# MCU.net
KiCad netlist of a schematic drawn in Altium Designer
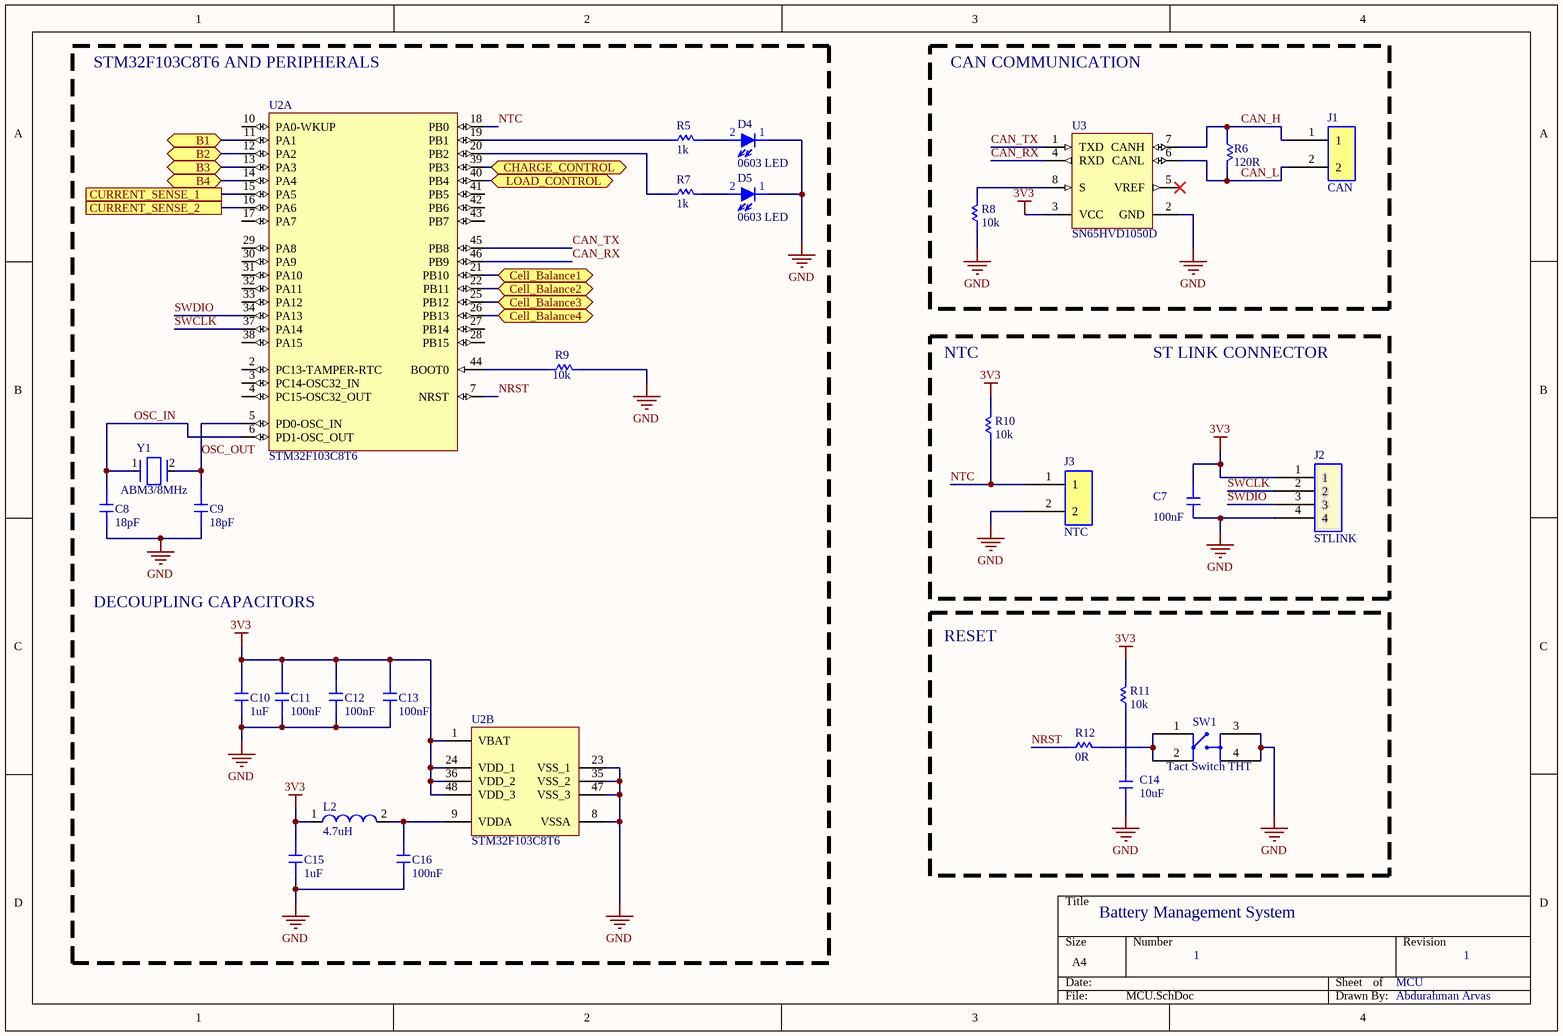
[diagram p0: MCU.SchDoc]

(export (version "E")
  (design (tool "Eeschema 10.0.6"))
  (components
    (comp (ref "C7")
      (value "100nF")
      (footprint "C0805")
      (libsource (lib "Arvas_AltiumSCH") (part "SMD_Capacitor"))
    )
    (comp (ref "C8")
      (value "18pF")
      (footprint "C0603")
      (libsource (lib "Arvas_AltiumSCH") (part "SMD_Capacitor"))
    )
    (comp (ref "C9")
      (value "18pF")
      (footprint "C0603")
      (libsource (lib "Arvas_AltiumSCH") (part "SMD_Capacitor"))
    )
    (comp (ref "C10")
      (value "1uF")
      (footprint "C0805")
      (libsource (lib "Arvas_AltiumSCH") (part "SMD_Capacitor"))
    )
    (comp (ref "C11")
      (value "100nF")
      (footprint "C0805")
      (libsource (lib "Arvas_AltiumSCH") (part "SMD_Capacitor"))
    )
    (comp (ref "C12")
      (value "100nF")
      (footprint "C0805")
      (libsource (lib "Arvas_AltiumSCH") (part "SMD_Capacitor"))
    )
    (comp (ref "C13")
      (value "100nF")
      (footprint "C0805")
      (libsource (lib "Arvas_AltiumSCH") (part "SMD_Capacitor"))
    )
    (comp (ref "C14")
      (value "10uF")
      (footprint "C0805")
      (libsource (lib "Arvas_AltiumSCH") (part "SMD_Capacitor"))
    )
    (comp (ref "C15")
      (value "1uF")
      (footprint "C0805")
      (libsource (lib "Arvas_AltiumSCH") (part "SMD_Capacitor"))
    )
    (comp (ref "C16")
      (value "100nF")
      (footprint "C0805")
      (libsource (lib "Arvas_AltiumSCH") (part "SMD_Capacitor"))
    )
    (comp (ref "D4")
      (value "0603 LED")
      (footprint "LED_0603")
      (description "Light Emitting Diode with 0603 footprint.")
      (libsource (lib "Arvas_AltiumSCH") (part "Led 0603"))
    )
    (comp (ref "D5")
      (value "0603 LED")
      (footprint "LED_0603")
      (description "Light Emitting Diode with 0603 footprint.")
      (libsource (lib "Arvas_AltiumSCH") (part "Led 0603"))
    )
    (comp (ref "J1")
      (value "CAN")
      (footprint "CONN X2")
      (description "İki Pin Connector")
      (libsource (lib "Arvas_AltiumSCH") (part "CONN X2_1"))
    )
    (comp (ref "J2")
      (value "STLINK")
      (footprint "CONN X4")
      (description "x4 Pin Header")
      (libsource (lib "Arvas_AltiumSCH") (part "CONN X4"))
    )
    (comp (ref "J3")
      (value "NTC")
      (footprint "CONN X2")
      (description "İki Pin Connector")
      (libsource (lib "Arvas_AltiumSCH") (part "CONN X2_1"))
    )
    (comp (ref "L2")
      (value "4.7uH")
      (footprint "SMD-0805")
      (description "SMD-Multilayer Inductor WE-MI, L = 1.00 µH")
      (libsource (lib "Altium Content Vault") (part "PAS-IND-INDUCTOR-2"))
    )
    (comp (ref "R5")
      (value "1k")
      (footprint "R0603")
      (description "SMD Chip Resistor")
      (libsource (lib "Arvas_AltiumSCH") (part "SMD Resistor"))
    )
    (comp (ref "R6")
      (value "120R")
      (footprint "R0805")
      (description "SMD Chip Resistor")
      (libsource (lib "Arvas_AltiumSCH") (part "SMD Resistor"))
    )
    (comp (ref "R7")
      (value "1k")
      (footprint "R0603")
      (description "SMD Chip Resistor")
      (libsource (lib "Arvas_AltiumSCH") (part "SMD Resistor"))
    )
    (comp (ref "R8")
      (value "10k")
      (footprint "R0805")
      (description "SMD Chip Resistor")
      (libsource (lib "Arvas_AltiumSCH") (part "SMD Resistor"))
    )
    (comp (ref "R9")
      (value "10k")
      (footprint "R0805")
      (description "SMD Chip Resistor")
      (libsource (lib "Arvas_AltiumSCH") (part "SMD Resistor"))
    )
    (comp (ref "R10")
      (value "10k")
      (footprint "R0805")
      (description "SMD Chip Resistor")
      (libsource (lib "Arvas_AltiumSCH") (part "SMD Resistor"))
    )
    (comp (ref "R11")
      (value "10k")
      (footprint "R0805")
      (description "SMD Chip Resistor")
      (libsource (lib "Arvas_AltiumSCH") (part "SMD Resistor"))
    )
    (comp (ref "R12")
      (value "0R")
      (footprint "R0805")
      (description "SMD Chip Resistor")
      (libsource (lib "Arvas_AltiumSCH") (part "SMD Resistor"))
    )
    (comp (ref "SW1")
      (value "Tact Switch THT")
      (footprint "Tact Switch 6x6 mm")
      (description "Tact Switch 6x6 mm")
      (libsource (lib "Arvas_AltiumSCH") (part "Tact Switch THT"))
    )
    (comp (ref "U2")
      (value "STM32F103C8T6")
      (footprint "STM-LQFP48_L")
      (libsource (lib "Altium Content Vault") (part "MC-ARM-STM32F103X8_B-SQ48"))
    )
    (comp (ref "U3")
      (value "SN65HVD1050D")
      (footprint "D0008A_N")
      (fields (field (name "MANUFACTURER") "Texas Instruments"))
      (libsource (lib "Altium Content Vault") (part "TI-SN65HVD1050-SOIC_D-8"))
    )
    (comp (ref "Y1")
      (value "ABM3/8MHz")
      (footprint "FP-ABM3-MFG")
      (description "Crystal 8MHz ±20ppm 18pF SMD-2 5mm x 3.2mm")
      (fields (field (name "TOLERANCE") "20ppm"))
      (libsource (lib "Altium Content Vault") (part "c23a69dc6c9e2f18f2079038eb95dd1"))
    )
  )
  (nets
    (net (code "1") (name "/B1") (class "Default")
      (node (ref "U2") (pin "11") (pinfunction "PA1_11") (pintype "bidirectional"))
    )
    (net (code "2") (name "/B2") (class "Default")
      (node (ref "U2") (pin "12") (pinfunction "PA2_12") (pintype "bidirectional"))
    )
    (net (code "3") (name "/B3") (class "Default")
      (node (ref "U2") (pin "13") (pinfunction "PA3_13") (pintype "bidirectional"))
    )
    (net (code "4") (name "/B4") (class "Default")
      (node (ref "U2") (pin "14") (pinfunction "PA4_14") (pintype "bidirectional"))
    )
    (net (code "5") (name "/CAN_H") (class "Default")
      (node (ref "J1") (pin "1") (pinfunction "1_1") (pintype "passive"))
      (node (ref "R6") (pin "1") (pinfunction "1_1") (pintype "passive"))
      (node (ref "U3") (pin "7") (pinfunction "CANH_7") (pintype "bidirectional"))
    )
    (net (code "6") (name "/CAN_L") (class "Default")
      (node (ref "J1") (pin "2") (pinfunction "2_2") (pintype "passive"))
      (node (ref "R6") (pin "2") (pinfunction "2_2") (pintype "passive"))
      (node (ref "U3") (pin "6") (pinfunction "CANL_6") (pintype "bidirectional"))
    )
    (net (code "7") (name "/CAN_RX") (class "Default")
      (node (ref "U2") (pin "46") (pinfunction "PB9_46") (pintype "bidirectional"))
      (node (ref "U3") (pin "4") (pinfunction "RXD_4") (pintype "output"))
    )
    (net (code "8") (name "/CAN_TX") (class "Default")
      (node (ref "U2") (pin "45") (pinfunction "PB8_45") (pintype "bidirectional"))
      (node (ref "U3") (pin "1") (pinfunction "TXD_1") (pintype "input"))
    )
    (net (code "9") (name "/CHARGE_CONTROL") (class "Default")
      (node (ref "U2") (pin "39") (pinfunction "PB3_39") (pintype "bidirectional"))
    )
    (net (code "10") (name "/CURRENT_SENSE_1") (class "Default")
      (node (ref "U2") (pin "15") (pinfunction "PA5_15") (pintype "bidirectional"))
    )
    (net (code "11") (name "/CURRENT_SENSE_2") (class "Default")
      (node (ref "U2") (pin "16") (pinfunction "PA6_16") (pintype "bidirectional"))
    )
    (net (code "12") (name "/Cell_Balance1") (class "Default")
      (node (ref "U2") (pin "21") (pinfunction "PB10_21") (pintype "bidirectional"))
    )
    (net (code "13") (name "/Cell_Balance2") (class "Default")
      (node (ref "U2") (pin "22") (pinfunction "PB11_22") (pintype "bidirectional"))
    )
    (net (code "14") (name "/Cell_Balance3") (class "Default")
      (node (ref "U2") (pin "25") (pinfunction "PB12_25") (pintype "bidirectional"))
    )
    (net (code "15") (name "/Cell_Balance4") (class "Default")
      (node (ref "U2") (pin "26") (pinfunction "PB13_26") (pintype "bidirectional"))
    )
    (net (code "16") (name "/LOAD_CONTROL") (class "Default")
      (node (ref "U2") (pin "40") (pinfunction "PB4_40") (pintype "bidirectional"))
    )
    (net (code "17") (name "/NRST") (class "Default")
      (node (ref "R12") (pin "1") (pinfunction "1_1") (pintype "passive"))
      (node (ref "U2") (pin "7") (pinfunction "NRST_7") (pintype "bidirectional"))
    )
    (net (code "18") (name "/NTC") (class "Default")
      (node (ref "J3") (pin "1") (pinfunction "1_1") (pintype "passive"))
      (node (ref "R10") (pin "1") (pinfunction "1_1") (pintype "passive"))
      (node (ref "U2") (pin "18") (pinfunction "PB0_18") (pintype "bidirectional"))
    )
    (net (code "19") (name "/OSC_IN") (class "Default")
      (node (ref "C8") (pin "2") (pinfunction "2_2") (pintype "passive"))
      (node (ref "U2") (pin "6") (pinfunction "PD1-OSC_OUT_6") (pintype "bidirectional"))
      (node (ref "Y1") (pin "1") (pinfunction "1_1") (pintype "passive"))
    )
    (net (code "20") (name "/OSC_OUT") (class "Default")
      (node (ref "C9") (pin "2") (pinfunction "2_2") (pintype "passive"))
      (node (ref "U2") (pin "5") (pinfunction "PD0-OSC_IN_5") (pintype "bidirectional"))
      (node (ref "Y1") (pin "2") (pinfunction "2_2") (pintype "passive"))
    )
    (net (code "21") (name "/SWCLK") (class "Default")
      (node (ref "J2") (pin "2") (pinfunction "2_2") (pintype "passive"))
      (node (ref "U2") (pin "37") (pinfunction "PA14_37") (pintype "bidirectional"))
    )
    (net (code "22") (name "/SWDIO") (class "Default")
      (node (ref "J2") (pin "3") (pinfunction "3_3") (pintype "passive"))
      (node (ref "U2") (pin "34") (pinfunction "PA13_34") (pintype "bidirectional"))
    )
    (net (code "23") (name "3V3") (class "Default")
      (node (ref "C10") (pin "2") (pinfunction "2_2") (pintype "passive"))
      (node (ref "C11") (pin "2") (pinfunction "2_2") (pintype "passive"))
      (node (ref "C12") (pin "2") (pinfunction "2_2") (pintype "passive"))
      (node (ref "C13") (pin "2") (pinfunction "2_2") (pintype "passive"))
      (node (ref "C15") (pin "2") (pinfunction "2_2") (pintype "passive"))
      (node (ref "C7") (pin "2") (pinfunction "2_2") (pintype "passive"))
      (node (ref "J2") (pin "1") (pinfunction "1_1") (pintype "passive"))
      (node (ref "L2") (pin "1") (pinfunction "1_1") (pintype "passive"))
      (node (ref "R10") (pin "2") (pinfunction "2_2") (pintype "passive"))
      (node (ref "R11") (pin "2") (pinfunction "2_2") (pintype "passive"))
      (node (ref "U2") (pin "1") (pinfunction "VBAT_1") (pintype "power_in"))
      (node (ref "U2") (pin "24") (pinfunction "VDD_1_24") (pintype "power_in"))
      (node (ref "U2") (pin "36") (pinfunction "VDD_2_36") (pintype "power_in"))
      (node (ref "U2") (pin "48") (pinfunction "VDD_3_48") (pintype "power_in"))
      (node (ref "U3") (pin "3") (pinfunction "VCC_3") (pintype "power_in"))
    )
    (net (code "24") (name "GND") (class "Default")
      (node (ref "C10") (pin "1") (pinfunction "1_1") (pintype "passive"))
      (node (ref "C11") (pin "1") (pinfunction "1_1") (pintype "passive"))
      (node (ref "C12") (pin "1") (pinfunction "1_1") (pintype "passive"))
      (node (ref "C13") (pin "1") (pinfunction "1_1") (pintype "passive"))
      (node (ref "C14") (pin "1") (pinfunction "1_1") (pintype "passive"))
      (node (ref "C15") (pin "1") (pinfunction "1_1") (pintype "passive"))
      (node (ref "C16") (pin "1") (pinfunction "1_1") (pintype "passive"))
      (node (ref "C7") (pin "1") (pinfunction "1_1") (pintype "passive"))
      (node (ref "C8") (pin "1") (pinfunction "1_1") (pintype "passive"))
      (node (ref "C9") (pin "1") (pinfunction "1_1") (pintype "passive"))
      (node (ref "D4") (pin "1") (pinfunction "Cathode_1") (pintype "passive"))
      (node (ref "D5") (pin "1") (pinfunction "Cathode_1") (pintype "passive"))
      (node (ref "J2") (pin "4") (pinfunction "4_4") (pintype "passive"))
      (node (ref "J3") (pin "2") (pinfunction "2_2") (pintype "passive"))
      (node (ref "R8") (pin "1") (pinfunction "1_1") (pintype "passive"))
      (node (ref "R9") (pin "2") (pinfunction "2_2") (pintype "passive"))
      (node (ref "SW1") (pin "3") (pintype "passive"))
      (node (ref "SW1") (pin "4") (pintype "passive"))
      (node (ref "U2") (pin "23") (pinfunction "VSS_1_23") (pintype "power_in"))
      (node (ref "U2") (pin "35") (pinfunction "VSS_2_35") (pintype "power_in"))
      (node (ref "U2") (pin "47") (pinfunction "VSS_3_47") (pintype "power_in"))
      (node (ref "U2") (pin "8") (pinfunction "VSSA_8") (pintype "power_in"))
      (node (ref "U3") (pin "2") (pinfunction "GND_2") (pintype "power_in"))
    )
    (net (code "25") (name "Net-(C14-Pad2)") (class "Default")
      (node (ref "C14") (pin "2") (pinfunction "2_2") (pintype "passive"))
      (node (ref "R11") (pin "1") (pinfunction "1_1") (pintype "passive"))
    )
    (net (code "26") (name "Net-(D4-Anode)") (class "Default")
      (node (ref "D4") (pin "2") (pinfunction "Anode_2") (pintype "passive"))
      (node (ref "R5") (pin "2") (pinfunction "2_2") (pintype "passive"))
    )
    (net (code "27") (name "Net-(D5-Anode)") (class "Default")
      (node (ref "D5") (pin "2") (pinfunction "Anode_2") (pintype "passive"))
      (node (ref "R7") (pin "2") (pinfunction "2_2") (pintype "passive"))
    )
    (net (code "28") (name "Net-(R12-Pad2)") (class "Default")
      (node (ref "R12") (pin "2") (pinfunction "2_2") (pintype "passive"))
      (node (ref "SW1") (pin "1") (pintype "passive"))
      (node (ref "SW1") (pin "2") (pintype "passive"))
    )
    (net (code "29") (name "Net-(U2A-BOOT0)") (class "Default")
      (node (ref "R9") (pin "1") (pinfunction "1_1") (pintype "passive"))
      (node (ref "U2") (pin "44") (pinfunction "BOOT0_44") (pintype "input"))
    )
    (net (code "30") (name "Net-(U2A-PB1)") (class "Default")
      (node (ref "R5") (pin "1") (pinfunction "1_1") (pintype "passive"))
      (node (ref "U2") (pin "19") (pinfunction "PB1_19") (pintype "bidirectional"))
    )
    (net (code "31") (name "Net-(U2A-PB2)") (class "Default")
      (node (ref "R7") (pin "1") (pinfunction "1_1") (pintype "passive"))
      (node (ref "U2") (pin "20") (pinfunction "PB2_20") (pintype "bidirectional"))
    )
    (net (code "32") (name "Net-(U2B-VDDA)") (class "Default")
      (node (ref "C16") (pin "2") (pinfunction "2_2") (pintype "passive"))
      (node (ref "L2") (pin "2") (pinfunction "2_2") (pintype "passive"))
      (node (ref "U2") (pin "9") (pinfunction "VDDA_9") (pintype "power_in"))
    )
    (net (code "33") (name "Net-(U3-S)") (class "Default")
      (node (ref "R8") (pin "2") (pinfunction "2_2") (pintype "passive"))
      (node (ref "U3") (pin "8") (pinfunction "S_8") (pintype "input"))
    )
    (net (code "34") (name "unconnected-(U2A-PA0-WKUP-Pad10)") (class "Default")
      (node (ref "U2") (pin "10") (pinfunction "PA0-WKUP_10") (pintype "bidirectional"))
    )
    (net (code "35") (name "unconnected-(U2A-PA7-Pad17)") (class "Default")
      (node (ref "U2") (pin "17") (pinfunction "PA7_17") (pintype "bidirectional"))
    )
    (net (code "36") (name "unconnected-(U2A-PA8-Pad29)") (class "Default")
      (node (ref "U2") (pin "29") (pinfunction "PA8_29") (pintype "bidirectional"))
    )
    (net (code "37") (name "unconnected-(U2A-PA9-Pad30)") (class "Default")
      (node (ref "U2") (pin "30") (pinfunction "PA9_30") (pintype "bidirectional"))
    )
    (net (code "38") (name "unconnected-(U2A-PA10-Pad31)") (class "Default")
      (node (ref "U2") (pin "31") (pinfunction "PA10_31") (pintype "bidirectional"))
    )
    (net (code "39") (name "unconnected-(U2A-PA11-Pad32)") (class "Default")
      (node (ref "U2") (pin "32") (pinfunction "PA11_32") (pintype "bidirectional"))
    )
    (net (code "40") (name "unconnected-(U2A-PA12-Pad33)") (class "Default")
      (node (ref "U2") (pin "33") (pinfunction "PA12_33") (pintype "bidirectional"))
    )
    (net (code "41") (name "unconnected-(U2A-PA15-Pad38)") (class "Default")
      (node (ref "U2") (pin "38") (pinfunction "PA15_38") (pintype "bidirectional"))
    )
    (net (code "42") (name "unconnected-(U2A-PB5-Pad41)") (class "Default")
      (node (ref "U2") (pin "41") (pinfunction "PB5_41") (pintype "bidirectional"))
    )
    (net (code "43") (name "unconnected-(U2A-PB6-Pad42)") (class "Default")
      (node (ref "U2") (pin "42") (pinfunction "PB6_42") (pintype "bidirectional"))
    )
    (net (code "44") (name "unconnected-(U2A-PB7-Pad43)") (class "Default")
      (node (ref "U2") (pin "43") (pinfunction "PB7_43") (pintype "bidirectional"))
    )
    (net (code "45") (name "unconnected-(U2A-PB14-Pad27)") (class "Default")
      (node (ref "U2") (pin "27") (pinfunction "PB14_27") (pintype "bidirectional"))
    )
    (net (code "46") (name "unconnected-(U2A-PB15-Pad28)") (class "Default")
      (node (ref "U2") (pin "28") (pinfunction "PB15_28") (pintype "bidirectional"))
    )
    (net (code "47") (name "unconnected-(U2A-PC13-TAMPER-RTC-Pad2)") (class "Default")
      (node (ref "U2") (pin "2") (pinfunction "PC13-TAMPER-RTC_2") (pintype "bidirectional"))
    )
    (net (code "48") (name "unconnected-(U2A-PC14-OSC32_IN-Pad3)") (class "Default")
      (node (ref "U2") (pin "3") (pinfunction "PC14-OSC32_IN_3") (pintype "bidirectional"))
    )
    (net (code "49") (name "unconnected-(U2A-PC15-OSC32_OUT-Pad4)") (class "Default")
      (node (ref "U2") (pin "4") (pinfunction "PC15-OSC32_OUT_4") (pintype "bidirectional"))
    )
    (net (code "50") (name "unconnected-(U3-VREF-Pad5)") (class "Default")
      (node (ref "U3") (pin "5") (pinfunction "VREF_5") (pintype "output+no_connect"))
    )
  )
)
